# BBB_Cape.net
KiCad netlist of a schematic drawn in Altium Designer
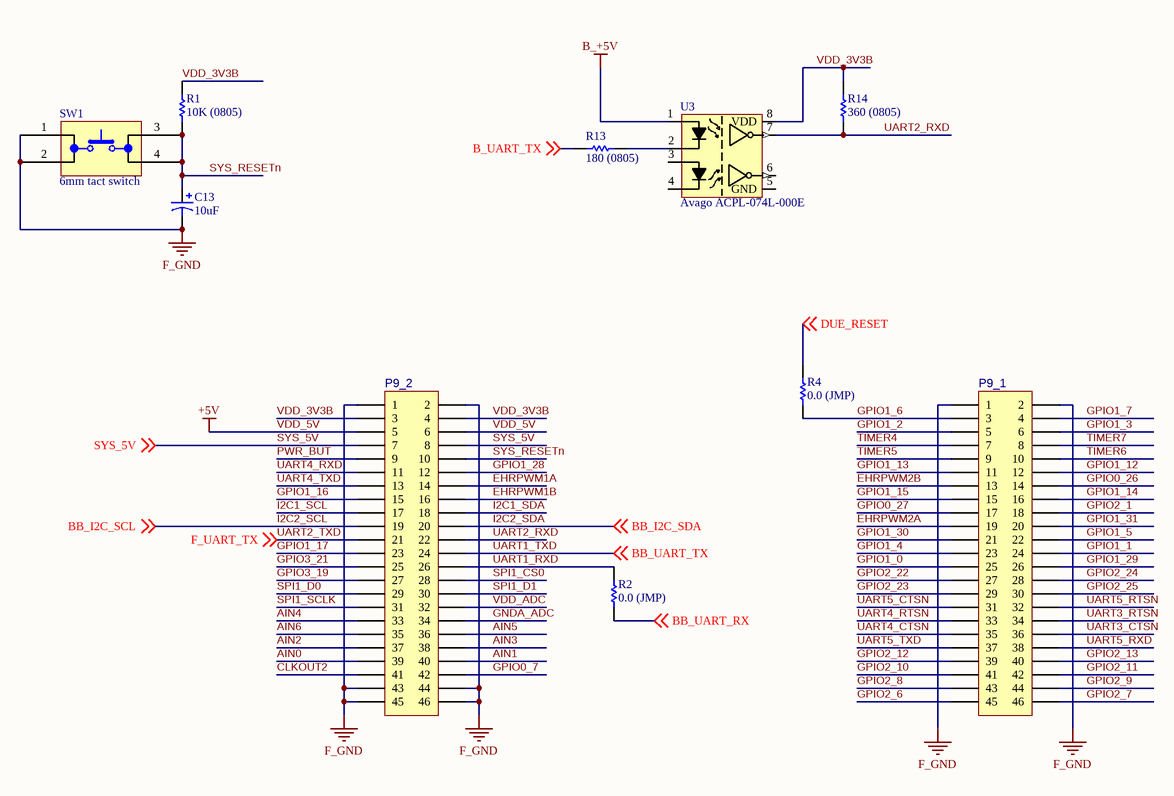
[diagram p0: BBB_Cape.SchDoc]

(export (version "E")
  (design (tool "Eeschema 10.0.6"))
  (components
    (comp (ref "C13")
      (value "10uF")
      (footprint "PCB-ibkib54e90xysjsqnert-1")
      (description "Capacitor Alum Elec, 10uf, 100v, 20%, Capacitor Alum Elec, 10uf, 100v, 20%, Smd, Full Reel")
      (fields (field (name "MANUFACTURER PART NUMBER") "EEE-2AA100UP"))
      (libsource (lib "CommunityVault") (part "SYM-da8810cd3d6e054f-1"))
    )
    (comp (ref "P9_1")
      (value "Major League Electronics TSHC-123-D-06-240-GT-LF")
      (footprint "PCB-44amy4d7xro60oo8ojyx-1")
      (description "TSHC series 46 position 2.54 mm straight Thru Hole Connector")
      (fields (field (name "MANUFACTURER PART NUMBER") "TSHC-123-D-06-240-GT-LF"))
      (libsource (lib "CommunityVault") (part "CMP-5fc8970d5e37800f-3"))
    )
    (comp (ref "P9_2")
      (value "Major League Electronics TSHC-123-D-06-240-GT-LF")
      (footprint "PCB-44amy4d7xro60oo8ojyx-1")
      (description "TSHC series 46 position 2.54 mm straight Thru Hole Connector")
      (fields (field (name "MANUFACTURER PART NUMBER") "TSHC-123-D-06-240-GT-LF"))
      (libsource (lib "CommunityVault") (part "CMP-5fc8970d5e37800f-3"))
    )
    (comp (ref "R1")
      (value "10K (0805)")
      (footprint "RESC2013X60X40NL15T20")
      (description "RES SMD 10K OHM 1% 1/3W 0805")
      (libsource (lib "FavoritesLibrary") (part "RES-2"))
    )
    (comp (ref "R2")
      (value "0.0 (JMP)")
      (footprint "RESC2013X60X35ML10T20")
      (description "Res Thick Film 0805 0 Ohm Molded SMD Paper T/R")
      (fields (field (name "MANUFACTURER PART NUMBER") "RC0805FR-070RL"))
      (libsource (lib "FavoritesLibrary") (part "SYM-f3d13a5618eb2c16-1"))
    )
    (comp (ref "R4")
      (value "0.0 (JMP)")
      (footprint "RESC2013X60X35ML10T20")
      (description "Res Thick Film 0805 0 Ohm Molded SMD Paper T/R")
      (fields (field (name "MANUFACTURER PART NUMBER") "RC0805FR-070RL"))
      (libsource (lib "FavoritesLibrary") (part "SYM-f3d13a5618eb2c16-1"))
    )
    (comp (ref "R13")
      (value "180 (0805)")
      (footprint "RESC2013X60X40NL15T20")
      (description "RES SMD 10K OHM 1% 1/3W 0805")
      (libsource (lib "FavoritesLibrary") (part "RES-2"))
    )
    (comp (ref "R14")
      (value "360 (0805)")
      (footprint "RESC2013X60X40NL15T20")
      (description "RES SMD 10K OHM 1% 1/3W 0805")
      (libsource (lib "FavoritesLibrary") (part "RES-2"))
    )
    (comp (ref "SW1")
      (value "6mm tact switch")
      (footprint "PCB-gaic1pl4705ifv3nefaq-1")
      (description "Switch Tactile OFF (ON) SPST Round Button PC Pins 0.05A 24VDC 100000Cycles 1.57N Thru-Hole Loose")
      (fields (field (name "MANUFACTURER PART NUMBER") "1825910-6"))
      (libsource (lib "FavoritesLibrary") (part "SYM-3ee8f78971b1e12f-3"))
    )
    (comp (ref "U3")
      (value "Avago ACPL-074L-000E")
      (footprint "PCB-tvxoajnlj650fdg499ex-1")
      (description "Optocoupler Logic-Out Push-Pull DC-IN 2-CH 8-Pin SOIC Tube")
      (fields (field (name "MANUFACTURER PART NUMBER") "ACPL-074L-000E"))
      (libsource (lib "FavoritesLibrary") (part "SYM-ee2b274cae1231ec-1"))
    )
  )
  (nets
    (net (code "1") (name "+5V") (class "Default")
      (node (ref "P9_2") (pin "5") (pinfunction "5_5") (pintype "passive"))
      (node (ref "P9_2") (pin "6") (pinfunction "6_6") (pintype "passive"))
    )
    (net (code "2") (name "/AIN0") (class "Default")
      (node (ref "P9_2") (pin "39") (pinfunction "39_39") (pintype "passive"))
    )
    (net (code "3") (name "/AIN1") (class "Default")
      (node (ref "P9_2") (pin "40") (pinfunction "40_40") (pintype "passive"))
    )
    (net (code "4") (name "/AIN2") (class "Default")
      (node (ref "P9_2") (pin "37") (pinfunction "37_37") (pintype "passive"))
    )
    (net (code "5") (name "/AIN3") (class "Default")
      (node (ref "P9_2") (pin "38") (pinfunction "38_38") (pintype "passive"))
    )
    (net (code "6") (name "/AIN4") (class "Default")
      (node (ref "P9_2") (pin "33") (pinfunction "33_33") (pintype "passive"))
    )
    (net (code "7") (name "/AIN5") (class "Default")
      (node (ref "P9_2") (pin "36") (pinfunction "36_36") (pintype "passive"))
    )
    (net (code "8") (name "/AIN6") (class "Default")
      (node (ref "P9_2") (pin "35") (pinfunction "35_35") (pintype "passive"))
    )
    (net (code "9") (name "/CLKOUT2") (class "Default")
      (node (ref "P9_2") (pin "41") (pinfunction "41_41") (pintype "passive"))
    )
    (net (code "10") (name "/EHRPWM1A") (class "Default")
      (node (ref "P9_2") (pin "14") (pinfunction "14_14") (pintype "passive"))
    )
    (net (code "11") (name "/EHRPWM1B") (class "Default")
      (node (ref "P9_2") (pin "16") (pinfunction "16_16") (pintype "passive"))
    )
    (net (code "12") (name "/EHRPWM2A") (class "Default")
      (node (ref "P9_1") (pin "19") (pinfunction "19_19") (pintype "passive"))
    )
    (net (code "13") (name "/EHRPWM2B") (class "Default")
      (node (ref "P9_1") (pin "13") (pinfunction "13_13") (pintype "passive"))
    )
    (net (code "14") (name "/GNDA_ADC") (class "Default")
      (node (ref "P9_2") (pin "34") (pinfunction "34_34") (pintype "passive"))
    )
    (net (code "15") (name "/GPIO0_7") (class "Default")
      (node (ref "P9_2") (pin "42") (pinfunction "42_42") (pintype "passive"))
    )
    (net (code "16") (name "/GPIO0_26") (class "Default")
      (node (ref "P9_1") (pin "14") (pinfunction "14_14") (pintype "passive"))
    )
    (net (code "17") (name "/GPIO0_27") (class "Default")
      (node (ref "P9_1") (pin "17") (pinfunction "17_17") (pintype "passive"))
    )
    (net (code "18") (name "/GPIO1_0") (class "Default")
      (node (ref "P9_1") (pin "25") (pinfunction "25_25") (pintype "passive"))
    )
    (net (code "19") (name "/GPIO1_1") (class "Default")
      (node (ref "P9_1") (pin "24") (pinfunction "24_24") (pintype "passive"))
    )
    (net (code "20") (name "/GPIO1_2") (class "Default")
      (node (ref "P9_1") (pin "5") (pinfunction "5_5") (pintype "passive"))
    )
    (net (code "21") (name "/GPIO1_3") (class "Default")
      (node (ref "P9_1") (pin "6") (pinfunction "6_6") (pintype "passive"))
    )
    (net (code "22") (name "/GPIO1_4") (class "Default")
      (node (ref "P9_1") (pin "23") (pinfunction "23_23") (pintype "passive"))
    )
    (net (code "23") (name "/GPIO1_5") (class "Default")
      (node (ref "P9_1") (pin "22") (pinfunction "22_22") (pintype "passive"))
    )
    (net (code "24") (name "/GPIO1_6") (class "Default")
      (node (ref "P9_1") (pin "3") (pinfunction "3_3") (pintype "passive"))
      (node (ref "R4") (pin "1") (pinfunction "1_1") (pintype "passive"))
    )
    (net (code "25") (name "/GPIO1_7") (class "Default")
      (node (ref "P9_1") (pin "4") (pinfunction "4_4") (pintype "passive"))
    )
    (net (code "26") (name "/GPIO1_12") (class "Default")
      (node (ref "P9_1") (pin "12") (pinfunction "12_12") (pintype "passive"))
    )
    (net (code "27") (name "/GPIO1_13") (class "Default")
      (node (ref "P9_1") (pin "11") (pinfunction "11_11") (pintype "passive"))
    )
    (net (code "28") (name "/GPIO1_14") (class "Default")
      (node (ref "P9_1") (pin "16") (pinfunction "16_16") (pintype "passive"))
    )
    (net (code "29") (name "/GPIO1_15") (class "Default")
      (node (ref "P9_1") (pin "15") (pinfunction "15_15") (pintype "passive"))
    )
    (net (code "30") (name "/GPIO1_16") (class "Default")
      (node (ref "P9_2") (pin "15") (pinfunction "15_15") (pintype "passive"))
    )
    (net (code "31") (name "/GPIO1_17") (class "Default")
      (node (ref "P9_2") (pin "23") (pinfunction "23_23") (pintype "passive"))
    )
    (net (code "32") (name "/GPIO1_28") (class "Default")
      (node (ref "P9_2") (pin "12") (pinfunction "12_12") (pintype "passive"))
    )
    (net (code "33") (name "/GPIO1_29") (class "Default")
      (node (ref "P9_1") (pin "26") (pinfunction "26_26") (pintype "passive"))
    )
    (net (code "34") (name "/GPIO1_30") (class "Default")
      (node (ref "P9_1") (pin "21") (pinfunction "21_21") (pintype "passive"))
    )
    (net (code "35") (name "/GPIO1_31") (class "Default")
      (node (ref "P9_1") (pin "20") (pinfunction "20_20") (pintype "passive"))
    )
    (net (code "36") (name "/GPIO2_1") (class "Default")
      (node (ref "P9_1") (pin "18") (pinfunction "18_18") (pintype "passive"))
    )
    (net (code "37") (name "/GPIO2_6") (class "Default")
      (node (ref "P9_1") (pin "45") (pinfunction "45_45") (pintype "passive"))
    )
    (net (code "38") (name "/GPIO2_7") (class "Default")
      (node (ref "P9_1") (pin "46") (pinfunction "46_46") (pintype "passive"))
    )
    (net (code "39") (name "/GPIO2_8") (class "Default")
      (node (ref "P9_1") (pin "43") (pinfunction "43_43") (pintype "passive"))
    )
    (net (code "40") (name "/GPIO2_9") (class "Default")
      (node (ref "P9_1") (pin "44") (pinfunction "44_44") (pintype "passive"))
    )
    (net (code "41") (name "/GPIO2_10") (class "Default")
      (node (ref "P9_1") (pin "41") (pinfunction "41_41") (pintype "passive"))
    )
    (net (code "42") (name "/GPIO2_11") (class "Default")
      (node (ref "P9_1") (pin "42") (pinfunction "42_42") (pintype "passive"))
    )
    (net (code "43") (name "/GPIO2_12") (class "Default")
      (node (ref "P9_1") (pin "39") (pinfunction "39_39") (pintype "passive"))
    )
    (net (code "44") (name "/GPIO2_13") (class "Default")
      (node (ref "P9_1") (pin "40") (pinfunction "40_40") (pintype "passive"))
    )
    (net (code "45") (name "/GPIO2_22") (class "Default")
      (node (ref "P9_1") (pin "27") (pinfunction "27_27") (pintype "passive"))
    )
    (net (code "46") (name "/GPIO2_23") (class "Default")
      (node (ref "P9_1") (pin "29") (pinfunction "29_29") (pintype "passive"))
    )
    (net (code "47") (name "/GPIO2_24") (class "Default")
      (node (ref "P9_1") (pin "28") (pinfunction "28_28") (pintype "passive"))
    )
    (net (code "48") (name "/GPIO2_25") (class "Default")
      (node (ref "P9_1") (pin "30") (pinfunction "30_30") (pintype "passive"))
    )
    (net (code "49") (name "/GPIO3_19") (class "Default")
      (node (ref "P9_2") (pin "27") (pinfunction "27_27") (pintype "passive"))
    )
    (net (code "50") (name "/GPIO3_21") (class "Default")
      (node (ref "P9_2") (pin "25") (pinfunction "25_25") (pintype "passive"))
    )
    (net (code "51") (name "/I2C1_SCL") (class "Default")
      (node (ref "P9_2") (pin "17") (pinfunction "17_17") (pintype "passive"))
    )
    (net (code "52") (name "/I2C1_SDA") (class "Default")
      (node (ref "P9_2") (pin "18") (pinfunction "18_18") (pintype "passive"))
    )
    (net (code "53") (name "/PWR_BUT") (class "Default")
      (node (ref "P9_2") (pin "9") (pinfunction "9_9") (pintype "passive"))
    )
    (net (code "54") (name "/SPI1_CS0") (class "Default")
      (node (ref "P9_2") (pin "28") (pinfunction "28_28") (pintype "passive"))
    )
    (net (code "55") (name "/SPI1_D0") (class "Default")
      (node (ref "P9_2") (pin "29") (pinfunction "29_29") (pintype "passive"))
    )
    (net (code "56") (name "/SPI1_D1") (class "Default")
      (node (ref "P9_2") (pin "30") (pinfunction "30_30") (pintype "passive"))
    )
    (net (code "57") (name "/SPI1_SCLK") (class "Default")
      (node (ref "P9_2") (pin "31") (pinfunction "31_31") (pintype "passive"))
    )
    (net (code "58") (name "/SYS_RESETn") (class "Default")
      (node (ref "C13") (pin "1") (pinfunction "1_1") (pintype "passive"))
      (node (ref "P9_2") (pin "10") (pinfunction "10_10") (pintype "passive"))
      (node (ref "R1") (pin "1") (pinfunction "1_1") (pintype "passive"))
      (node (ref "SW1") (pin "3") (pinfunction "3_3") (pintype "passive"))
      (node (ref "SW1") (pin "4") (pinfunction "4_4") (pintype "passive"))
    )
    (net (code "59") (name "/TIMER4") (class "Default")
      (node (ref "P9_1") (pin "7") (pinfunction "7_7") (pintype "passive"))
    )
    (net (code "60") (name "/TIMER5") (class "Default")
      (node (ref "P9_1") (pin "9") (pinfunction "9_9") (pintype "passive"))
    )
    (net (code "61") (name "/TIMER6") (class "Default")
      (node (ref "P9_1") (pin "10") (pinfunction "10_10") (pintype "passive"))
    )
    (net (code "62") (name "/TIMER7") (class "Default")
      (node (ref "P9_1") (pin "8") (pinfunction "8_8") (pintype "passive"))
    )
    (net (code "63") (name "/UART1_RXD") (class "Default")
      (node (ref "P9_2") (pin "26") (pinfunction "26_26") (pintype "passive"))
      (node (ref "R2") (pin "2") (pinfunction "2_2") (pintype "passive"))
    )
    (net (code "64") (name "/UART2_RXD") (class "Default")
      (node (ref "P9_2") (pin "22") (pinfunction "22_22") (pintype "passive"))
      (node (ref "R14") (pin "2") (pinfunction "2_2") (pintype "passive"))
      (node (ref "U3") (pin "7") (pinfunction "7_7") (pintype "output"))
    )
    (net (code "65") (name "/UART3_CTSN") (class "Default")
      (node (ref "P9_1") (pin "36") (pinfunction "36_36") (pintype "passive"))
    )
    (net (code "66") (name "/UART3_RTSN") (class "Default")
      (node (ref "P9_1") (pin "34") (pinfunction "34_34") (pintype "passive"))
    )
    (net (code "67") (name "/UART4_CTSN") (class "Default")
      (node (ref "P9_1") (pin "35") (pinfunction "35_35") (pintype "passive"))
    )
    (net (code "68") (name "/UART4_RTSN") (class "Default")
      (node (ref "P9_1") (pin "33") (pinfunction "33_33") (pintype "passive"))
    )
    (net (code "69") (name "/UART4_RXD") (class "Default")
      (node (ref "P9_2") (pin "11") (pinfunction "11_11") (pintype "passive"))
    )
    (net (code "70") (name "/UART4_TXD") (class "Default")
      (node (ref "P9_2") (pin "13") (pinfunction "13_13") (pintype "passive"))
    )
    (net (code "71") (name "/UART5_CTSN") (class "Default")
      (node (ref "P9_1") (pin "31") (pinfunction "31_31") (pintype "passive"))
    )
    (net (code "72") (name "/UART5_RTSN") (class "Default")
      (node (ref "P9_1") (pin "32") (pinfunction "32_32") (pintype "passive"))
    )
    (net (code "73") (name "/UART5_RXD") (class "Default")
      (node (ref "P9_1") (pin "38") (pinfunction "38_38") (pintype "passive"))
    )
    (net (code "74") (name "/UART5_TXD") (class "Default")
      (node (ref "P9_1") (pin "37") (pinfunction "37_37") (pintype "passive"))
    )
    (net (code "75") (name "/VDD_3V3B") (class "Default")
      (node (ref "P9_2") (pin "3") (pinfunction "3_3") (pintype "passive"))
      (node (ref "P9_2") (pin "4") (pinfunction "4_4") (pintype "passive"))
      (node (ref "R1") (pin "2") (pinfunction "2_2") (pintype "passive"))
      (node (ref "R14") (pin "1") (pinfunction "1_1") (pintype "passive"))
      (node (ref "U3") (pin "8") (pinfunction "VDD_8") (pintype "passive"))
    )
    (net (code "76") (name "/VDD_ADC") (class "Default")
      (node (ref "P9_2") (pin "32") (pinfunction "32_32") (pintype "passive"))
    )
    (net (code "77") (name "BB_I2C_SCL") (class "Default")
      (node (ref "P9_2") (pin "19") (pinfunction "19_19") (pintype "passive"))
    )
    (net (code "78") (name "BB_I2C_SDA") (class "Default")
      (node (ref "P9_2") (pin "20") (pinfunction "20_20") (pintype "passive"))
    )
    (net (code "79") (name "BB_UART_RX") (class "Default")
      (node (ref "R2") (pin "1") (pinfunction "1_1") (pintype "passive"))
    )
    (net (code "80") (name "BB_UART_TX") (class "Default")
      (node (ref "P9_2") (pin "24") (pinfunction "24_24") (pintype "passive"))
    )
    (net (code "81") (name "B_+5V") (class "Default")
      (node (ref "U3") (pin "1") (pinfunction "1_1") (pintype "passive"))
    )
    (net (code "82") (name "B_UART_TX") (class "Default")
      (node (ref "R13") (pin "2") (pinfunction "2_2") (pintype "passive"))
    )
    (net (code "83") (name "DUE_RESET") (class "Default")
      (node (ref "R4") (pin "2") (pinfunction "2_2") (pintype "passive"))
    )
    (net (code "84") (name "F_GND") (class "Default")
      (node (ref "C13") (pin "2") (pinfunction "2_2") (pintype "passive"))
      (node (ref "P9_1") (pin "1") (pinfunction "1_1") (pintype "passive"))
      (node (ref "P9_1") (pin "2") (pinfunction "2_2") (pintype "passive"))
      (node (ref "P9_2") (pin "1") (pinfunction "1_1") (pintype "passive"))
      (node (ref "P9_2") (pin "2") (pinfunction "2_2") (pintype "passive"))
      (node (ref "P9_2") (pin "43") (pinfunction "43_43") (pintype "passive"))
      (node (ref "P9_2") (pin "44") (pinfunction "44_44") (pintype "passive"))
      (node (ref "P9_2") (pin "45") (pinfunction "45_45") (pintype "passive"))
      (node (ref "P9_2") (pin "46") (pinfunction "46_46") (pintype "passive"))
      (node (ref "SW1") (pin "1") (pinfunction "1_1") (pintype "passive"))
      (node (ref "SW1") (pin "2") (pinfunction "2_2") (pintype "passive"))
    )
    (net (code "85") (name "F_UART_TX") (class "Default")
      (node (ref "P9_2") (pin "21") (pinfunction "21_21") (pintype "passive"))
    )
    (net (code "86") (name "Net-(R13-Pad1)") (class "Default")
      (node (ref "R13") (pin "1") (pinfunction "1_1") (pintype "passive"))
      (node (ref "U3") (pin "2") (pinfunction "2_2") (pintype "passive"))
    )
    (net (code "87") (name "SYS_5V") (class "Default")
      (node (ref "P9_2") (pin "7") (pinfunction "7_7") (pintype "passive"))
      (node (ref "P9_2") (pin "8") (pinfunction "8_8") (pintype "passive"))
    )
    (net (code "88") (name "unconnected-(U3-GND-Pad5)") (class "Default")
      (node (ref "U3") (pin "5") (pinfunction "GND_5") (pintype "passive"))
    )
    (net (code "89") (name "unconnected-(U3-Pad3)") (class "Default")
      (node (ref "U3") (pin "3") (pinfunction "3_3") (pintype "passive"))
    )
    (net (code "90") (name "unconnected-(U3-Pad4)") (class "Default")
      (node (ref "U3") (pin "4") (pinfunction "4_4") (pintype "passive"))
    )
    (net (code "91") (name "unconnected-(U3-Pad6)") (class "Default")
      (node (ref "U3") (pin "6") (pinfunction "6_6") (pintype "output"))
    )
  )
)
